# RC_reciever.net
KiCad netlist of a schematic drawn in Altium Designer
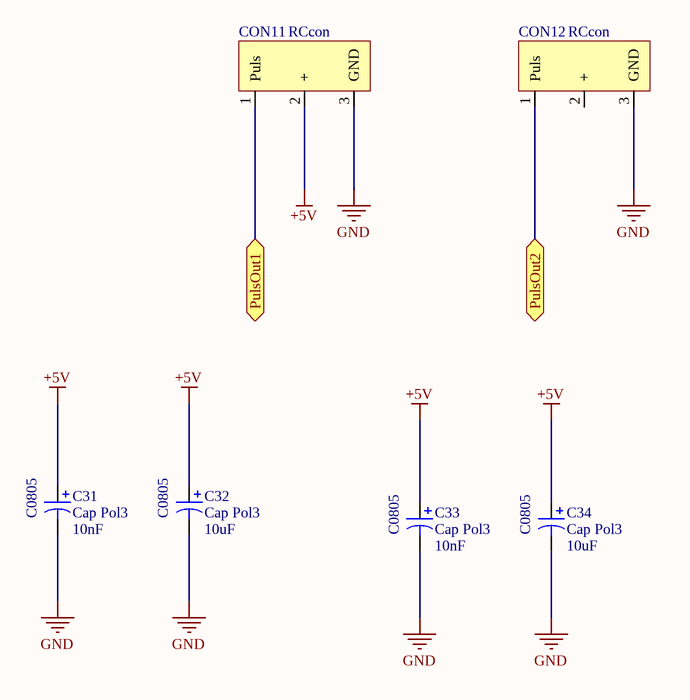
[diagram p0: RC reciever.SchDoc]

(export (version "E")
  (design (tool "Eeschema 10.0.6"))
  (components
    (comp (ref "C31")
      (value "Cap Pol3")
      (footprint "C0805")
      (description "Polarized Capacitor (Surface Mount)")
      (fields
        (field (name "PACKAGEREFERENCE") "C0805")
        (field (name "ALTIUM_VALUE") "10nF")
        (field (name "PUBLISHER") "Altium Limited")
      )
      (libsource (lib "Miscellaneous Devices") (part "Cap Pol3"))
    )
    (comp (ref "C32")
      (value "Cap Pol3")
      (footprint "C0805")
      (description "Polarized Capacitor (Surface Mount)")
      (fields
        (field (name "PACKAGEREFERENCE") "C0805")
        (field (name "ALTIUM_VALUE") "10uF")
        (field (name "PUBLISHER") "Altium Limited")
      )
      (libsource (lib "Miscellaneous Devices") (part "Cap Pol3"))
    )
    (comp (ref "C33")
      (value "Cap Pol3")
      (footprint "C0805")
      (description "Polarized Capacitor (Surface Mount)")
      (fields
        (field (name "PACKAGEREFERENCE") "C0805")
        (field (name "ALTIUM_VALUE") "10nF")
        (field (name "PUBLISHER") "Altium Limited")
      )
      (libsource (lib "Miscellaneous Devices") (part "Cap Pol3"))
    )
    (comp (ref "C34")
      (value "Cap Pol3")
      (footprint "C0805")
      (description "Polarized Capacitor (Surface Mount)")
      (fields
        (field (name "PACKAGEREFERENCE") "C0805")
        (field (name "ALTIUM_VALUE") "10uF")
        (field (name "PUBLISHER") "Altium Limited")
      )
      (libsource (lib "Miscellaneous Devices") (part "Cap Pol3"))
    )
    (comp (ref "CON11") (value "RCcon") (footprint "RcCon") (libsource (lib "RcCon") (part "Rc con")))
    (comp (ref "CON12") (value "RCcon") (footprint "RcCon") (libsource (lib "RcCon") (part "Rc con")))
  )
  (nets
    (net (code "1") (name "+5V") (class "Default")
      (node (ref "C31") (pin "1") (pinfunction "1_1") (pintype "passive"))
      (node (ref "C32") (pin "1") (pinfunction "1_1") (pintype "passive"))
      (node (ref "C33") (pin "1") (pinfunction "1_1") (pintype "passive"))
      (node (ref "C34") (pin "1") (pinfunction "1_1") (pintype "passive"))
      (node (ref "CON11") (pin "2") (pinfunction "+_2") (pintype "passive"))
    )
    (net (code "2") (name "/PulsOut1") (class "Default")
      (node (ref "CON11") (pin "1") (pinfunction "Puls_1") (pintype "passive"))
    )
    (net (code "3") (name "/PulsOut2") (class "Default")
      (node (ref "CON12") (pin "1") (pinfunction "Puls_1") (pintype "passive"))
    )
    (net (code "4") (name "GND") (class "Default")
      (node (ref "C31") (pin "2") (pinfunction "2_2") (pintype "passive"))
      (node (ref "C32") (pin "2") (pinfunction "2_2") (pintype "passive"))
      (node (ref "C33") (pin "2") (pinfunction "2_2") (pintype "passive"))
      (node (ref "C34") (pin "2") (pinfunction "2_2") (pintype "passive"))
      (node (ref "CON11") (pin "3") (pinfunction "GND_3") (pintype "passive"))
      (node (ref "CON12") (pin "3") (pinfunction "GND_3") (pintype "passive"))
    )
    (net (code "5") (name "unconnected-(CON12-+-Pad2)") (class "Default")
      (node (ref "CON12") (pin "2") (pinfunction "+_2") (pintype "passive"))
    )
  )
)
